# AND.net
KiCad netlist of a schematic drawn in EAGLE
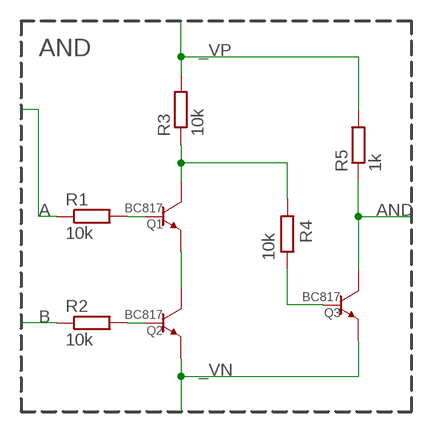
[diagram p0: schematic, sheet 1]

(export (version "E")
  (design (tool "Eeschema 10.0.6"))
  (components
    (comp (ref "Q1")
      (value "BC817")
      (footprint "eagle-import:SOT23")
      (libsource (lib "eagle-import") (part "TRANSISTOR-NPN-GENERIC-SOT23-BECDEFAULT"))
    )
    (comp (ref "Q2")
      (value "BC817")
      (footprint "eagle-import:SOT23")
      (libsource (lib "eagle-import") (part "TRANSISTOR-NPN-GENERIC-SOT23-BECDEFAULT"))
    )
    (comp (ref "Q3")
      (value "BC817")
      (footprint "eagle-import:SOT23")
      (libsource (lib "eagle-import") (part "TRANSISTOR-NPN-GENERIC-SOT23-BECDEFAULT"))
    )
    (comp (ref "R1")
      (value "10k")
      (footprint "eagle-import:R0603")
      (libsource (lib "eagle-import") (part "R-EU_R0603"))
    )
    (comp (ref "R2")
      (value "10k")
      (footprint "eagle-import:R0603")
      (libsource (lib "eagle-import") (part "R-EU_R0603"))
    )
    (comp (ref "R3")
      (value "10k")
      (footprint "eagle-import:R0603")
      (libsource (lib "eagle-import") (part "R-EU_R0603"))
    )
    (comp (ref "R4")
      (value "10k")
      (footprint "eagle-import:R0603")
      (libsource (lib "eagle-import") (part "R-EU_R0603"))
    )
    (comp (ref "R5")
      (value "1k")
      (footprint "eagle-import:R0603")
      (libsource (lib "eagle-import") (part "R-EU_R0603"))
    )
  )
  (nets
    (net (code "1") (name "/A") (class "Default")
      (node (ref "R1") (pin "1") (pinfunction "1_1") (pintype "passive"))
    )
    (net (code "2") (name "/AND") (class "Default")
      (node (ref "Q3") (pin "P$3") (pinfunction "COLLECTOR_P$3") (pintype "bidirectional"))
      (node (ref "R5") (pin "1") (pinfunction "1_1") (pintype "passive"))
    )
    (net (code "3") (name "/B") (class "Default")
      (node (ref "R2") (pin "1") (pinfunction "1_1") (pintype "passive"))
    )
    (net (code "4") (name "/_VN") (class "Default")
      (node (ref "Q2") (pin "P$2") (pinfunction "EMITTER_P$2") (pintype "bidirectional"))
      (node (ref "Q3") (pin "P$2") (pinfunction "EMITTER_P$2") (pintype "bidirectional"))
    )
    (net (code "5") (name "/_VP") (class "Default")
      (node (ref "R3") (pin "2") (pinfunction "2_2") (pintype "passive"))
      (node (ref "R5") (pin "2") (pinfunction "2_2") (pintype "passive"))
    )
    (net (code "6") (name "Net-(Q1-BASE)") (class "Default")
      (node (ref "Q1") (pin "P$1") (pinfunction "BASE_P$1") (pintype "bidirectional"))
      (node (ref "R1") (pin "2") (pinfunction "2_2") (pintype "passive"))
    )
    (net (code "7") (name "Net-(Q1-COLLECTOR)") (class "Default")
      (node (ref "Q1") (pin "P$3") (pinfunction "COLLECTOR_P$3") (pintype "bidirectional"))
      (node (ref "R3") (pin "1") (pinfunction "1_1") (pintype "passive"))
      (node (ref "R4") (pin "2") (pinfunction "2_2") (pintype "passive"))
    )
    (net (code "8") (name "Net-(Q1-EMITTER)") (class "Default")
      (node (ref "Q1") (pin "P$2") (pinfunction "EMITTER_P$2") (pintype "bidirectional"))
      (node (ref "Q2") (pin "P$3") (pinfunction "COLLECTOR_P$3") (pintype "bidirectional"))
    )
    (net (code "9") (name "Net-(Q2-BASE)") (class "Default")
      (node (ref "Q2") (pin "P$1") (pinfunction "BASE_P$1") (pintype "bidirectional"))
      (node (ref "R2") (pin "2") (pinfunction "2_2") (pintype "passive"))
    )
    (net (code "10") (name "Net-(Q3-BASE)") (class "Default")
      (node (ref "Q3") (pin "P$1") (pinfunction "BASE_P$1") (pintype "bidirectional"))
      (node (ref "R4") (pin "1") (pinfunction "1_1") (pintype "passive"))
    )
  )
)
